# camera.net
KiCad netlist of a schematic drawn in EAGLE
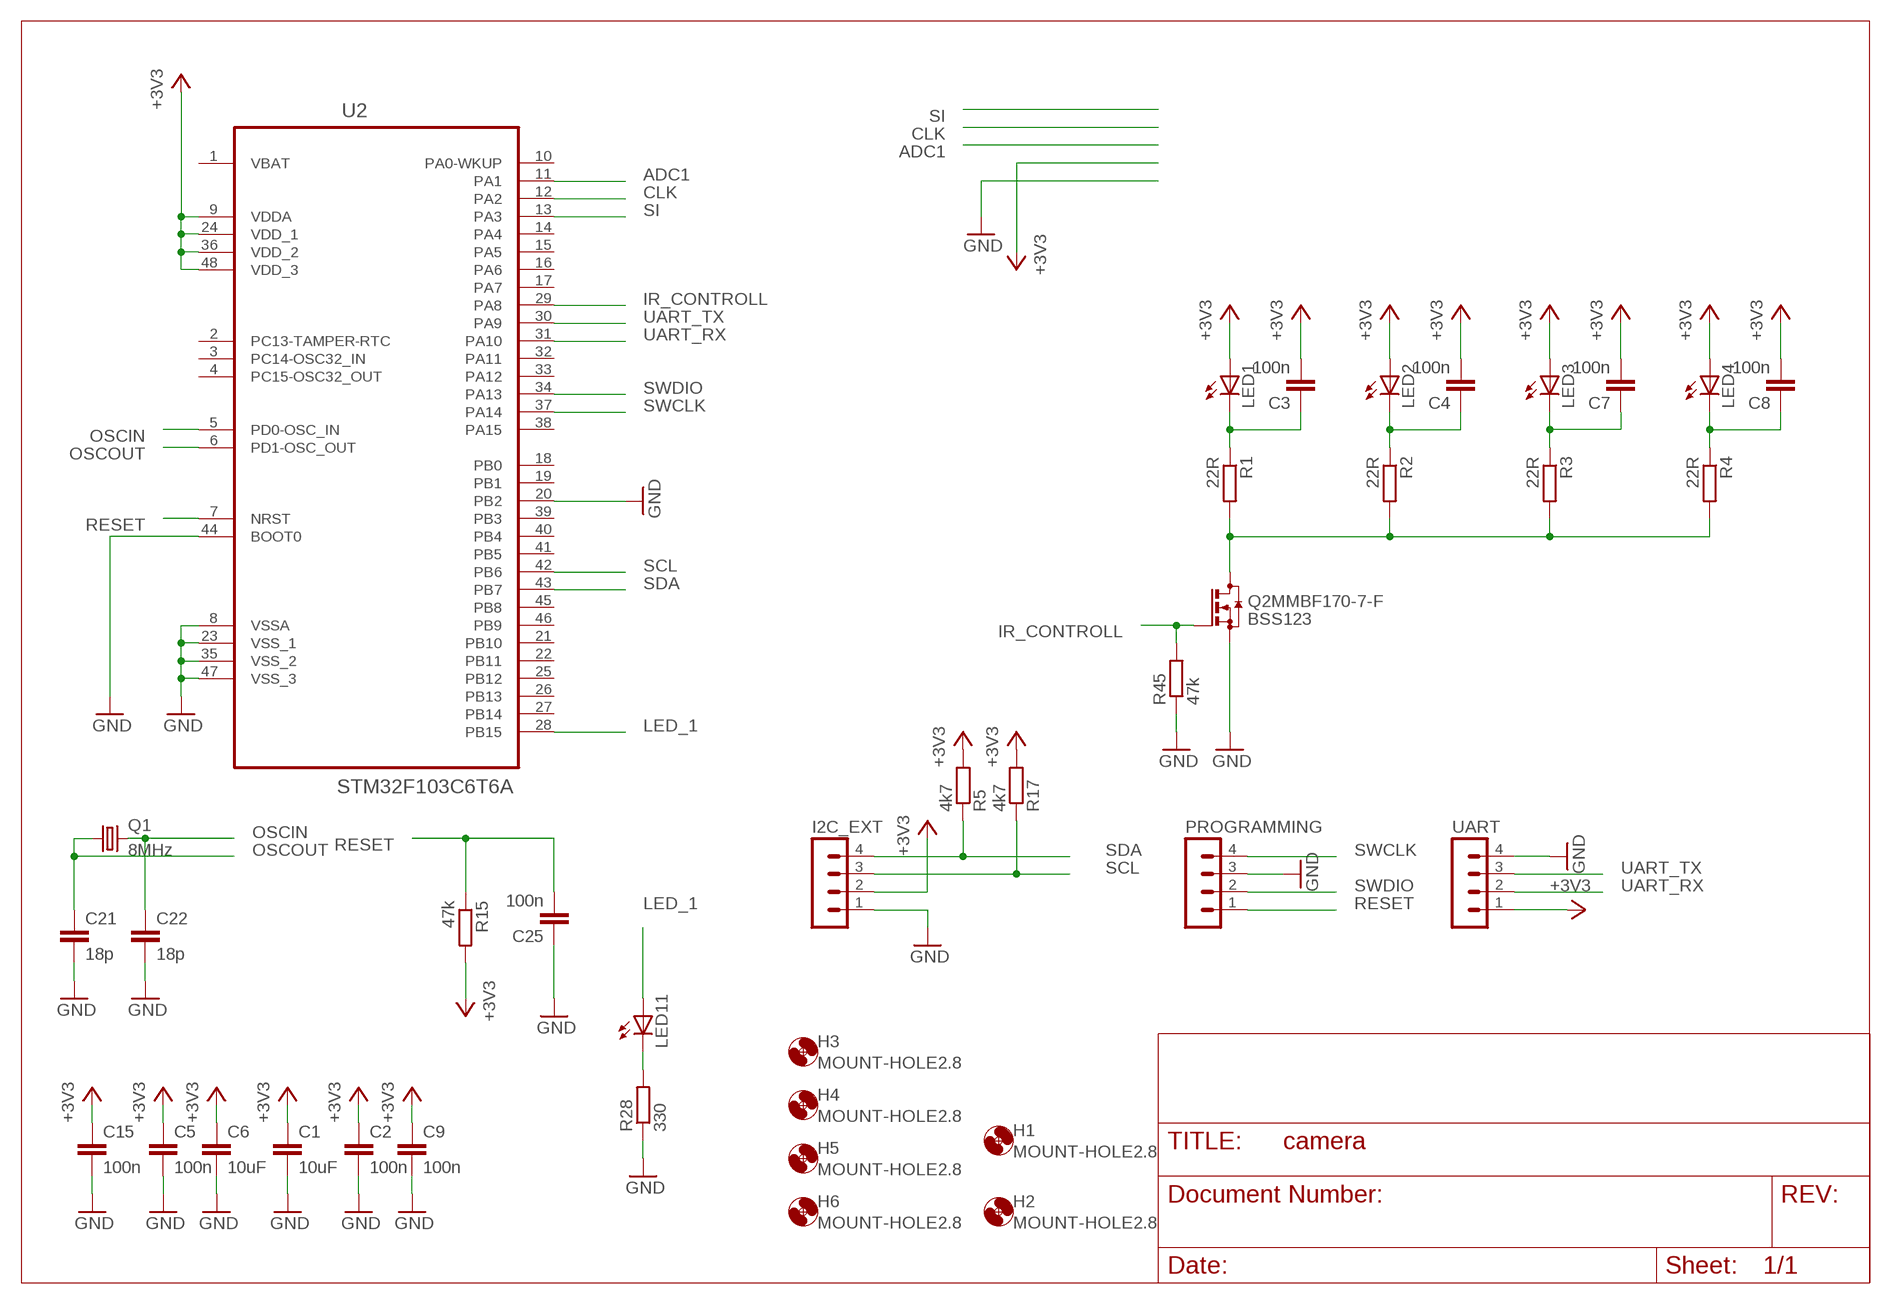
[diagram p0: schematic, sheet 1]

(export (version "E")
  (design (tool "Eeschema 10.0.6"))
  (components
    (comp (ref "C1")
      (value "10uF")
      (footprint "eagle-import:C0805")
      (libsource (lib "eagle-import") (part "C-EUC0805"))
    )
    (comp (ref "C2")
      (value "100n")
      (footprint "eagle-import:C0805")
      (libsource (lib "eagle-import") (part "C-EUC0805"))
    )
    (comp (ref "C3")
      (value "100n")
      (footprint "eagle-import:C0805")
      (libsource (lib "eagle-import") (part "C-EUC0805"))
    )
    (comp (ref "C4")
      (value "100n")
      (footprint "eagle-import:C0805")
      (libsource (lib "eagle-import") (part "C-EUC0805"))
    )
    (comp (ref "C5")
      (value "100n")
      (footprint "eagle-import:C0805")
      (libsource (lib "eagle-import") (part "C-EUC0805"))
    )
    (comp (ref "C6")
      (value "10uF")
      (footprint "eagle-import:C0805")
      (libsource (lib "eagle-import") (part "C-EUC0805"))
    )
    (comp (ref "C7")
      (value "100n")
      (footprint "eagle-import:C0805")
      (libsource (lib "eagle-import") (part "C-EUC0805"))
    )
    (comp (ref "C8")
      (value "100n")
      (footprint "eagle-import:C0805")
      (libsource (lib "eagle-import") (part "C-EUC0805"))
    )
    (comp (ref "C9")
      (value "100n")
      (footprint "eagle-import:C0805")
      (libsource (lib "eagle-import") (part "C-EUC0805"))
    )
    (comp (ref "C15")
      (value "100n")
      (footprint "eagle-import:C0805")
      (libsource (lib "eagle-import") (part "C-EUC0805"))
    )
    (comp (ref "C21")
      (value "18p")
      (footprint "eagle-import:C0805")
      (libsource (lib "eagle-import") (part "C-EUC0805"))
    )
    (comp (ref "C22")
      (value "18p")
      (footprint "eagle-import:C0805")
      (libsource (lib "eagle-import") (part "C-EUC0805"))
    )
    (comp (ref "C25")
      (value "100n")
      (footprint "eagle-import:C0805")
      (libsource (lib "eagle-import") (part "C-EUC0805"))
    )
    (comp (ref "H1")
      (value "MOUNT-HOLE2.8")
      (footprint "eagle-import:2,8")
      (libsource (lib "eagle-import") (part "MOUNT-HOLE2.8"))
    )
    (comp (ref "H2")
      (value "MOUNT-HOLE2.8")
      (footprint "eagle-import:2,8")
      (libsource (lib "eagle-import") (part "MOUNT-HOLE2.8"))
    )
    (comp (ref "H3")
      (value "MOUNT-HOLE2.8")
      (footprint "eagle-import:2,8")
      (libsource (lib "eagle-import") (part "MOUNT-HOLE2.8"))
    )
    (comp (ref "H4")
      (value "MOUNT-HOLE2.8")
      (footprint "eagle-import:2,8")
      (libsource (lib "eagle-import") (part "MOUNT-HOLE2.8"))
    )
    (comp (ref "H5")
      (value "MOUNT-HOLE2.8")
      (footprint "eagle-import:2,8")
      (libsource (lib "eagle-import") (part "MOUNT-HOLE2.8"))
    )
    (comp (ref "H6")
      (value "MOUNT-HOLE2.8")
      (footprint "eagle-import:2,8")
      (libsource (lib "eagle-import") (part "MOUNT-HOLE2.8"))
    )
    (comp (ref "I2C_EXT")
      (value "MA04-1")
      (footprint "eagle-import:MA04-1")
      (libsource (lib "eagle-import") (part "MA04-1"))
    )
    (comp (ref "LED1")
      (value "LED5MM")
      (footprint "eagle-import:LED5MM")
      (libsource (lib "eagle-import") (part "LED5MM"))
    )
    (comp (ref "LED2")
      (value "LED5MM")
      (footprint "eagle-import:LED5MM")
      (libsource (lib "eagle-import") (part "LED5MM"))
    )
    (comp (ref "LED3")
      (value "LED5MM")
      (footprint "eagle-import:LED5MM")
      (libsource (lib "eagle-import") (part "LED5MM"))
    )
    (comp (ref "LED4")
      (value "LED5MM")
      (footprint "eagle-import:LED5MM")
      (libsource (lib "eagle-import") (part "LED5MM"))
    )
    (comp (ref "LED11")
      (value "LEDCHIPLED_1206")
      (footprint "eagle-import:CHIPLED_1206")
      (libsource (lib "eagle-import") (part "LEDCHIPLED_1206"))
    )
    (comp (ref "PROGRAMMING")
      (value "MA04-1")
      (footprint "eagle-import:MA04-1")
      (libsource (lib "eagle-import") (part "MA04-1"))
    )
    (comp (ref "Q1")
      (value "8MHz")
      (footprint "eagle-import:CTS406")
      (libsource (lib "eagle-import") (part "CRYSTALCTS406"))
    )
    (comp (ref "Q2MMBF170-7-F")
      (value "BSS123")
      (footprint "eagle-import:SOT23")
      (libsource (lib "eagle-import") (part "BSS123"))
    )
    (comp (ref "R1")
      (value "22R")
      (footprint "eagle-import:M0805")
      (libsource (lib "eagle-import") (part "R-EU_M0805"))
    )
    (comp (ref "R2")
      (value "22R")
      (footprint "eagle-import:M0805")
      (libsource (lib "eagle-import") (part "R-EU_M0805"))
    )
    (comp (ref "R3")
      (value "22R")
      (footprint "eagle-import:M0805")
      (libsource (lib "eagle-import") (part "R-EU_M0805"))
    )
    (comp (ref "R4")
      (value "22R")
      (footprint "eagle-import:M0805")
      (libsource (lib "eagle-import") (part "R-EU_M0805"))
    )
    (comp (ref "R5")
      (value "4k7")
      (footprint "eagle-import:M0805")
      (libsource (lib "eagle-import") (part "R-EU_M0805"))
    )
    (comp (ref "R15")
      (value "47k")
      (footprint "eagle-import:M0805")
      (libsource (lib "eagle-import") (part "R-EU_M0805"))
    )
    (comp (ref "R17")
      (value "4k7")
      (footprint "eagle-import:M0805")
      (libsource (lib "eagle-import") (part "R-EU_M0805"))
    )
    (comp (ref "R28")
      (value "330")
      (footprint "eagle-import:M0805")
      (libsource (lib "eagle-import") (part "R-EU_M0805"))
    )
    (comp (ref "R45")
      (value "47k")
      (footprint "eagle-import:M0805")
      (libsource (lib "eagle-import") (part "R-EU_M0805"))
    )
    (comp (ref "U2")
      (value "STM32F103C6T6A")
      (footprint "eagle-import:QFP50P900X900X160-48N")
      (libsource (lib "eagle-import") (part "STM32F103C6T6A"))
    )
    (comp (ref "UART")
      (value "MA04-1")
      (footprint "eagle-import:MA04-1")
      (libsource (lib "eagle-import") (part "MA04-1"))
    )
  )
  (nets
    (net (code "1") (name "+3V3") (class "Default")
      (node (ref "C1") (pin "1") (pinfunction "1_1") (pintype "passive"))
      (node (ref "C15") (pin "1") (pinfunction "1_1") (pintype "passive"))
      (node (ref "C2") (pin "1") (pinfunction "1_1") (pintype "passive"))
      (node (ref "C3") (pin "2") (pinfunction "2_2") (pintype "passive"))
      (node (ref "C4") (pin "2") (pinfunction "2_2") (pintype "passive"))
      (node (ref "C5") (pin "1") (pinfunction "1_1") (pintype "passive"))
      (node (ref "C6") (pin "1") (pinfunction "1_1") (pintype "passive"))
      (node (ref "C7") (pin "2") (pinfunction "2_2") (pintype "passive"))
      (node (ref "C8") (pin "2") (pinfunction "2_2") (pintype "passive"))
      (node (ref "C9") (pin "1") (pinfunction "1_1") (pintype "passive"))
      (node (ref "I2C_EXT") (pin "2") (pinfunction "2_2") (pintype "passive"))
      (node (ref "LED1") (pin "A") (pinfunction "A_A") (pintype "passive"))
      (node (ref "LED2") (pin "A") (pinfunction "A_A") (pintype "passive"))
      (node (ref "LED3") (pin "A") (pinfunction "A_A") (pintype "passive"))
      (node (ref "LED4") (pin "A") (pinfunction "A_A") (pintype "passive"))
      (node (ref "R15") (pin "2") (pinfunction "2_2") (pintype "passive"))
      (node (ref "R17") (pin "2") (pinfunction "2_2") (pintype "passive"))
      (node (ref "R5") (pin "2") (pinfunction "2_2") (pintype "passive"))
      (node (ref "U2") (pin "24") (pinfunction "VDD_1_24") (pintype "power_in"))
      (node (ref "U2") (pin "36") (pinfunction "VDD_2_36") (pintype "power_in"))
      (node (ref "U2") (pin "48") (pinfunction "VDD_3_48") (pintype "power_in"))
      (node (ref "U2") (pin "9") (pinfunction "VDDA_9") (pintype "power_in"))
      (node (ref "UART") (pin "1") (pinfunction "1_1") (pintype "passive"))
    )
    (net (code "2") (name "/ADC1") (class "Default")
      (node (ref "U2") (pin "11") (pinfunction "PA1_11") (pintype "bidirectional"))
    )
    (net (code "3") (name "/CLK") (class "Default")
      (node (ref "U2") (pin "12") (pinfunction "PA2_12") (pintype "bidirectional"))
    )
    (net (code "4") (name "/IR_CONTROLL") (class "Default")
      (node (ref "Q2MMBF170-7-F") (pin "1") (pinfunction "G_1") (pintype "passive"))
      (node (ref "R45") (pin "2") (pinfunction "2_2") (pintype "passive"))
      (node (ref "U2") (pin "29") (pinfunction "PA8_29") (pintype "bidirectional"))
    )
    (net (code "5") (name "/LED_1") (class "Default")
      (node (ref "LED11") (pin "A") (pinfunction "A_A") (pintype "passive"))
      (node (ref "U2") (pin "28") (pinfunction "PB15_28") (pintype "bidirectional"))
    )
    (net (code "6") (name "/OSCIN") (class "Default")
      (node (ref "C22") (pin "1") (pinfunction "1_1") (pintype "passive"))
      (node (ref "Q1") (pin "3") (pinfunction "2_3") (pintype "passive"))
      (node (ref "U2") (pin "5") (pinfunction "PD0-OSC_IN_5") (pintype "bidirectional"))
    )
    (net (code "7") (name "/OSCOUT") (class "Default")
      (node (ref "C21") (pin "1") (pinfunction "1_1") (pintype "passive"))
      (node (ref "Q1") (pin "1") (pinfunction "1_1") (pintype "passive"))
      (node (ref "U2") (pin "6") (pinfunction "PD1-OSC_OUT_6") (pintype "bidirectional"))
    )
    (net (code "8") (name "/RESET") (class "Default")
      (node (ref "C25") (pin "2") (pinfunction "2_2") (pintype "passive"))
      (node (ref "PROGRAMMING") (pin "1") (pinfunction "1_1") (pintype "passive"))
      (node (ref "R15") (pin "1") (pinfunction "1_1") (pintype "passive"))
      (node (ref "U2") (pin "7") (pinfunction "NRST_7") (pintype "bidirectional"))
    )
    (net (code "9") (name "/SCL") (class "Default")
      (node (ref "I2C_EXT") (pin "3") (pinfunction "3_3") (pintype "passive"))
      (node (ref "R17") (pin "1") (pinfunction "1_1") (pintype "passive"))
      (node (ref "U2") (pin "42") (pinfunction "PB6_42") (pintype "bidirectional"))
    )
    (net (code "10") (name "/SDA") (class "Default")
      (node (ref "I2C_EXT") (pin "4") (pinfunction "4_4") (pintype "passive"))
      (node (ref "R5") (pin "1") (pinfunction "1_1") (pintype "passive"))
      (node (ref "U2") (pin "43") (pinfunction "PB7_43") (pintype "bidirectional"))
    )
    (net (code "11") (name "/SI") (class "Default")
      (node (ref "U2") (pin "13") (pinfunction "PA3_13") (pintype "bidirectional"))
    )
    (net (code "12") (name "/SWCLK") (class "Default")
      (node (ref "PROGRAMMING") (pin "4") (pinfunction "4_4") (pintype "passive"))
      (node (ref "U2") (pin "37") (pinfunction "PA14_37") (pintype "bidirectional"))
    )
    (net (code "13") (name "/SWDIO") (class "Default")
      (node (ref "PROGRAMMING") (pin "2") (pinfunction "2_2") (pintype "passive"))
      (node (ref "U2") (pin "34") (pinfunction "PA13_34") (pintype "bidirectional"))
    )
    (net (code "14") (name "/UART_RX") (class "Default")
      (node (ref "U2") (pin "31") (pinfunction "PA10_31") (pintype "bidirectional"))
      (node (ref "UART") (pin "2") (pinfunction "2_2") (pintype "passive"))
    )
    (net (code "15") (name "/UART_TX") (class "Default")
      (node (ref "U2") (pin "30") (pinfunction "PA9_30") (pintype "bidirectional"))
      (node (ref "UART") (pin "3") (pinfunction "3_3") (pintype "passive"))
    )
    (net (code "16") (name "/VBAT") (class "Default")
      (node (ref "U2") (pin "1") (pinfunction "VBAT_1") (pintype "power_in"))
    )
    (net (code "17") (name "GND") (class "Default")
      (node (ref "C1") (pin "2") (pinfunction "2_2") (pintype "passive"))
      (node (ref "C15") (pin "2") (pinfunction "2_2") (pintype "passive"))
      (node (ref "C2") (pin "2") (pinfunction "2_2") (pintype "passive"))
      (node (ref "C21") (pin "2") (pinfunction "2_2") (pintype "passive"))
      (node (ref "C22") (pin "2") (pinfunction "2_2") (pintype "passive"))
      (node (ref "C25") (pin "1") (pinfunction "1_1") (pintype "passive"))
      (node (ref "C5") (pin "2") (pinfunction "2_2") (pintype "passive"))
      (node (ref "C6") (pin "2") (pinfunction "2_2") (pintype "passive"))
      (node (ref "C9") (pin "2") (pinfunction "2_2") (pintype "passive"))
      (node (ref "I2C_EXT") (pin "1") (pinfunction "1_1") (pintype "passive"))
      (node (ref "PROGRAMMING") (pin "3") (pinfunction "3_3") (pintype "passive"))
      (node (ref "Q2MMBF170-7-F") (pin "2") (pinfunction "S_2") (pintype "passive"))
      (node (ref "R28") (pin "1") (pinfunction "1_1") (pintype "passive"))
      (node (ref "R45") (pin "1") (pinfunction "1_1") (pintype "passive"))
      (node (ref "U2") (pin "20") (pinfunction "PB2_20") (pintype "bidirectional"))
      (node (ref "U2") (pin "23") (pinfunction "VSS_1_23") (pintype "passive"))
      (node (ref "U2") (pin "35") (pinfunction "VSS_2_35") (pintype "passive"))
      (node (ref "U2") (pin "44") (pinfunction "BOOT0_44") (pintype "input"))
      (node (ref "U2") (pin "47") (pinfunction "VSS_3_47") (pintype "passive"))
      (node (ref "U2") (pin "8") (pinfunction "VSSA_8") (pintype "passive"))
      (node (ref "UART") (pin "4") (pinfunction "4_4") (pintype "passive"))
    )
    (net (code "18") (name "Net-(LED1-C)") (class "Default")
      (node (ref "C3") (pin "1") (pinfunction "1_1") (pintype "passive"))
      (node (ref "LED1") (pin "K") (pinfunction "C_K") (pintype "passive"))
      (node (ref "R1") (pin "1") (pinfunction "1_1") (pintype "passive"))
    )
    (net (code "19") (name "Net-(LED2-C)") (class "Default")
      (node (ref "C4") (pin "1") (pinfunction "1_1") (pintype "passive"))
      (node (ref "LED2") (pin "K") (pinfunction "C_K") (pintype "passive"))
      (node (ref "R2") (pin "1") (pinfunction "1_1") (pintype "passive"))
    )
    (net (code "20") (name "Net-(LED3-C)") (class "Default")
      (node (ref "C7") (pin "1") (pinfunction "1_1") (pintype "passive"))
      (node (ref "LED3") (pin "K") (pinfunction "C_K") (pintype "passive"))
      (node (ref "R3") (pin "1") (pinfunction "1_1") (pintype "passive"))
    )
    (net (code "21") (name "Net-(LED4-C)") (class "Default")
      (node (ref "C8") (pin "1") (pinfunction "1_1") (pintype "passive"))
      (node (ref "LED4") (pin "K") (pinfunction "C_K") (pintype "passive"))
      (node (ref "R4") (pin "1") (pinfunction "1_1") (pintype "passive"))
    )
    (net (code "22") (name "Net-(LED11-PadC)") (class "Default")
      (node (ref "LED11") (pin "C") (pinfunction "C_C") (pintype "passive"))
      (node (ref "R28") (pin "2") (pinfunction "2_2") (pintype "passive"))
    )
    (net (code "23") (name "Net-(Q2MMBF170-7-F-D)") (class "Default")
      (node (ref "Q2MMBF170-7-F") (pin "3") (pinfunction "D_3") (pintype "passive"))
      (node (ref "R1") (pin "2") (pinfunction "2_2") (pintype "passive"))
      (node (ref "R2") (pin "2") (pinfunction "2_2") (pintype "passive"))
      (node (ref "R3") (pin "2") (pinfunction "2_2") (pintype "passive"))
      (node (ref "R4") (pin "2") (pinfunction "2_2") (pintype "passive"))
    )
    (net (code "24") (name "unconnected-(U2-PA0-WKUP-Pad10)") (class "Default")
      (node (ref "U2") (pin "10") (pinfunction "PA0-WKUP_10") (pintype "bidirectional"))
    )
    (net (code "25") (name "unconnected-(U2-PA4-Pad14)") (class "Default")
      (node (ref "U2") (pin "14") (pinfunction "PA4_14") (pintype "bidirectional"))
    )
    (net (code "26") (name "unconnected-(U2-PA5-Pad15)") (class "Default")
      (node (ref "U2") (pin "15") (pinfunction "PA5_15") (pintype "bidirectional"))
    )
    (net (code "27") (name "unconnected-(U2-PA6-Pad16)") (class "Default")
      (node (ref "U2") (pin "16") (pinfunction "PA6_16") (pintype "bidirectional"))
    )
    (net (code "28") (name "unconnected-(U2-PA7-Pad17)") (class "Default")
      (node (ref "U2") (pin "17") (pinfunction "PA7_17") (pintype "bidirectional"))
    )
    (net (code "29") (name "unconnected-(U2-PA11-Pad32)") (class "Default")
      (node (ref "U2") (pin "32") (pinfunction "PA11_32") (pintype "bidirectional"))
    )
    (net (code "30") (name "unconnected-(U2-PA12-Pad33)") (class "Default")
      (node (ref "U2") (pin "33") (pinfunction "PA12_33") (pintype "bidirectional"))
    )
    (net (code "31") (name "unconnected-(U2-PA15-Pad38)") (class "Default")
      (node (ref "U2") (pin "38") (pinfunction "PA15_38") (pintype "bidirectional"))
    )
    (net (code "32") (name "unconnected-(U2-PB0-Pad18)") (class "Default")
      (node (ref "U2") (pin "18") (pinfunction "PB0_18") (pintype "bidirectional"))
    )
    (net (code "33") (name "unconnected-(U2-PB1-Pad19)") (class "Default")
      (node (ref "U2") (pin "19") (pinfunction "PB1_19") (pintype "bidirectional"))
    )
    (net (code "34") (name "unconnected-(U2-PB3-Pad39)") (class "Default")
      (node (ref "U2") (pin "39") (pinfunction "PB3_39") (pintype "bidirectional"))
    )
    (net (code "35") (name "unconnected-(U2-PB4-Pad40)") (class "Default")
      (node (ref "U2") (pin "40") (pinfunction "PB4_40") (pintype "bidirectional"))
    )
    (net (code "36") (name "unconnected-(U2-PB5-Pad41)") (class "Default")
      (node (ref "U2") (pin "41") (pinfunction "PB5_41") (pintype "bidirectional"))
    )
    (net (code "37") (name "unconnected-(U2-PB8-Pad45)") (class "Default")
      (node (ref "U2") (pin "45") (pinfunction "PB8_45") (pintype "bidirectional"))
    )
    (net (code "38") (name "unconnected-(U2-PB9-Pad46)") (class "Default")
      (node (ref "U2") (pin "46") (pinfunction "PB9_46") (pintype "bidirectional"))
    )
    (net (code "39") (name "unconnected-(U2-PB10-Pad21)") (class "Default")
      (node (ref "U2") (pin "21") (pinfunction "PB10_21") (pintype "bidirectional"))
    )
    (net (code "40") (name "unconnected-(U2-PB11-Pad22)") (class "Default")
      (node (ref "U2") (pin "22") (pinfunction "PB11_22") (pintype "bidirectional"))
    )
    (net (code "41") (name "unconnected-(U2-PB12-Pad25)") (class "Default")
      (node (ref "U2") (pin "25") (pinfunction "PB12_25") (pintype "bidirectional"))
    )
    (net (code "42") (name "unconnected-(U2-PB13-Pad26)") (class "Default")
      (node (ref "U2") (pin "26") (pinfunction "PB13_26") (pintype "bidirectional"))
    )
    (net (code "43") (name "unconnected-(U2-PB14-Pad27)") (class "Default")
      (node (ref "U2") (pin "27") (pinfunction "PB14_27") (pintype "bidirectional"))
    )
    (net (code "44") (name "unconnected-(U2-PC13-TAMPER-RTC-Pad2)") (class "Default")
      (node (ref "U2") (pin "2") (pinfunction "PC13-TAMPER-RTC_2") (pintype "bidirectional"))
    )
    (net (code "45") (name "unconnected-(U2-PC14-OSC32_IN-Pad3)") (class "Default")
      (node (ref "U2") (pin "3") (pinfunction "PC14-OSC32_IN_3") (pintype "bidirectional"))
    )
    (net (code "46") (name "unconnected-(U2-PC15-OSC32_OUT-Pad4)") (class "Default")
      (node (ref "U2") (pin "4") (pinfunction "PC15-OSC32_OUT_4") (pintype "bidirectional"))
    )
  )
)
